# expLoRaBLE_Thing_Plus.net
KiCad netlist of a schematic drawn in EAGLE
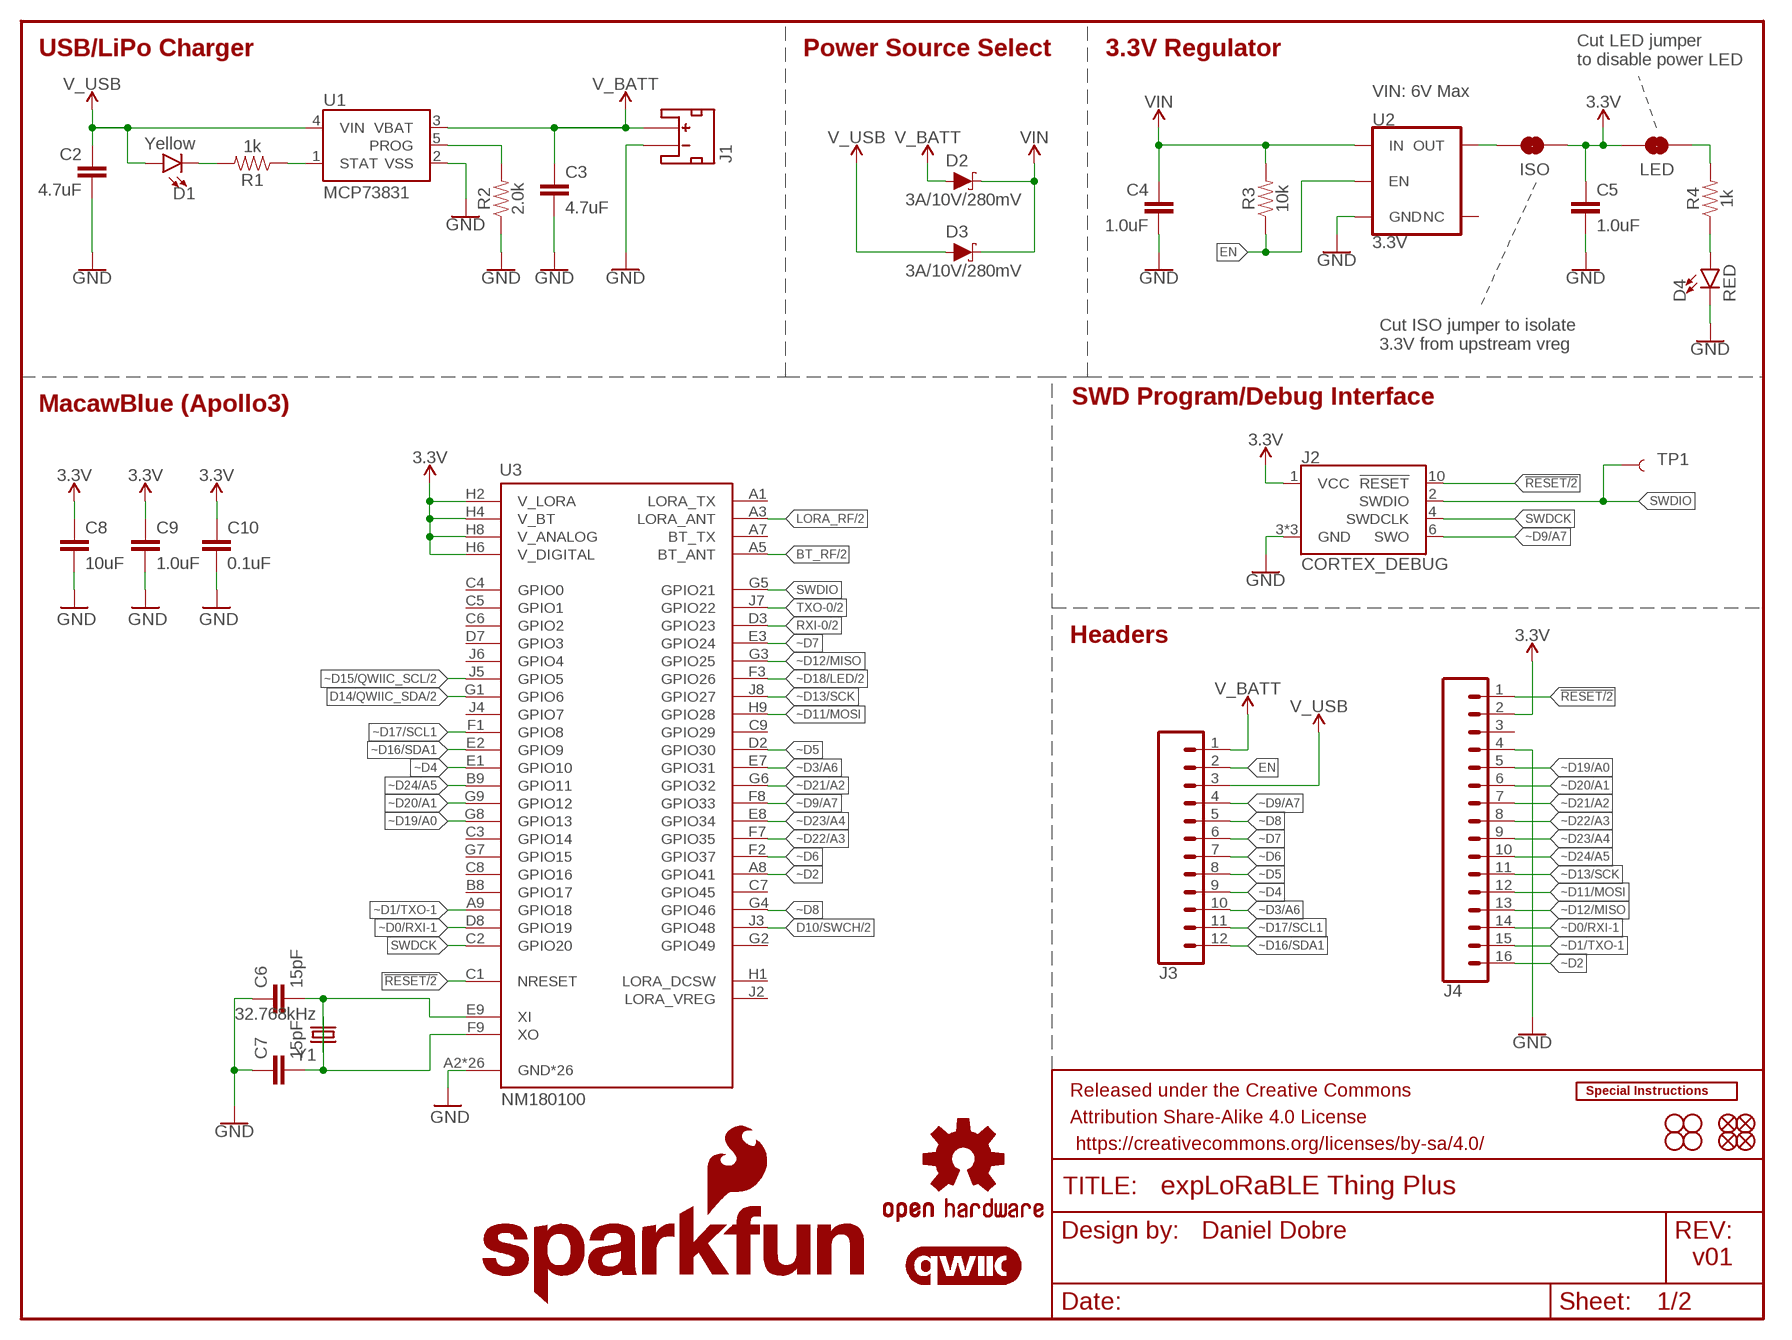
[diagram p0: schematic, sheet 1]
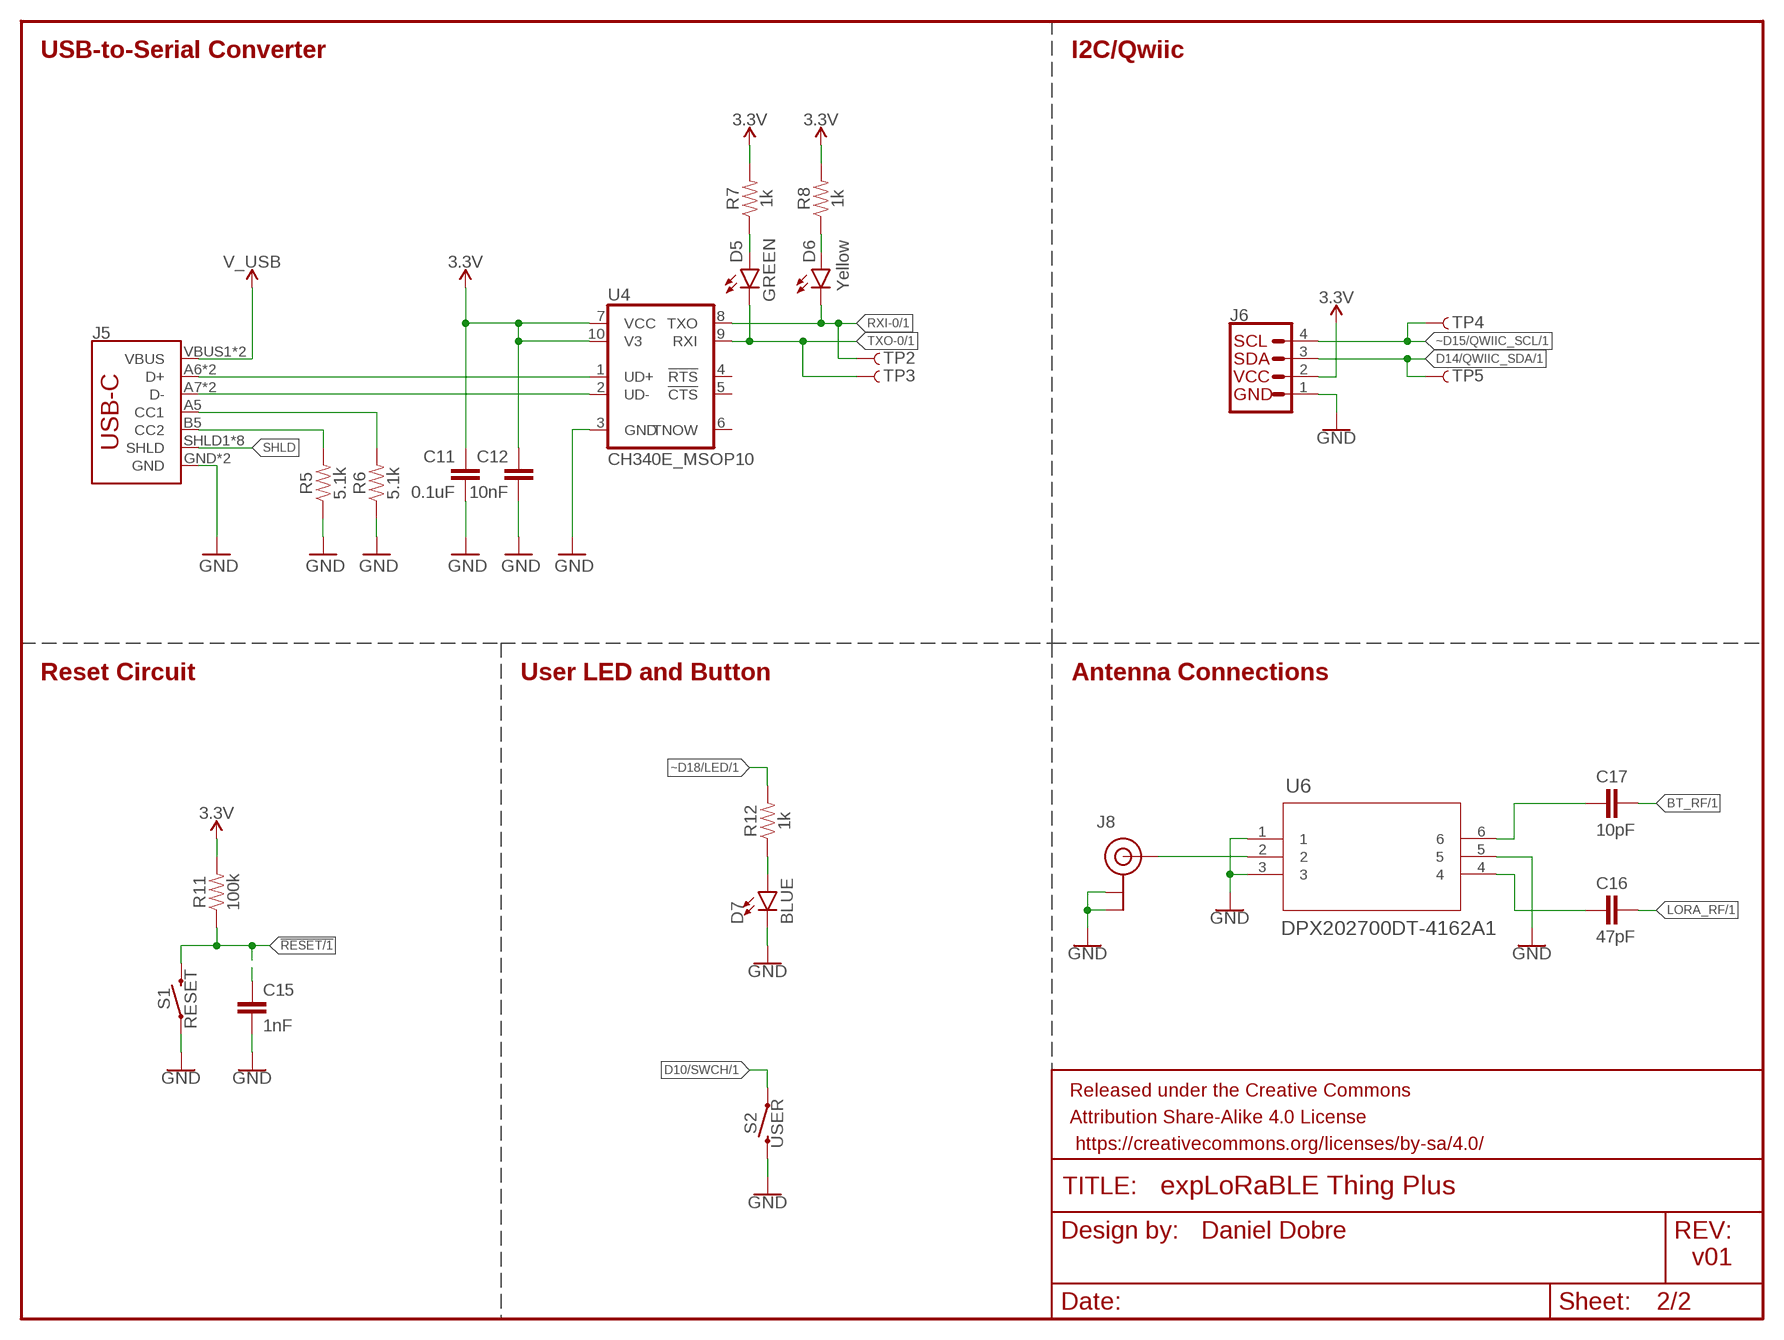
[diagram p1: schematic, sheet 2]

(export (version "E")
  (design (tool "Eeschema 10.0.6"))
  (components
    (comp (ref "C11")
      (value "0.1uF")
      (footprint "eagle-import:0603")
      (libsource (lib "eagle-import") (part "0.1UF-0603-25V-(+80/-20%)"))
    )
    (comp (ref "C12")
      (value "10nF")
      (footprint "eagle-import:0603")
      (libsource (lib "eagle-import") (part "10NF-0603-50V-10%"))
    )
    (comp (ref "C15")
      (value "1nF")
      (footprint "eagle-import:0603")
      (libsource (lib "eagle-import") (part "1.0NF/1000PF-0603-50V-10%"))
    )
    (comp (ref "C16")
      (value "47pF")
      (footprint "eagle-import:0603")
      (libsource (lib "eagle-import") (part "47PF-0603-50V-5%"))
    )
    (comp (ref "C17")
      (value "10pF")
      (footprint "eagle-import:0603")
      (libsource (lib "eagle-import") (part "10PF-0603-50V-5%"))
    )
    (comp (ref "D5")
      (value "GREEN")
      (footprint "eagle-import:LED-0603")
      (libsource (lib "eagle-import") (part "LED-GREEN0603"))
    )
    (comp (ref "D6")
      (value "Yellow")
      (footprint "eagle-import:LED-0603")
      (libsource (lib "eagle-import") (part "LED-YELLOW0603"))
    )
    (comp (ref "D7")
      (value "BLUE")
      (footprint "eagle-import:LED-0603")
      (libsource (lib "eagle-import") (part "LED-BLUE0603"))
    )
    (comp (ref "FRAME2")
      (value "FRAME-LETTERNO_PACKAGE")
      (footprint "eagle-import:DUMMY")
      (fields (field (name "DESIGNER") "Nobody"))
      (libsource (lib "eagle-import") (part "FRAME-LETTERNO_PACKAGE"))
    )
    (comp (ref "J5")
      (value "USB-C")
      (footprint "eagle-import:USB-C-16P")
      (libsource (lib "eagle-import") (part "USB_C2-LAYER"))
    )
    (comp (ref "J6")
      (value "QWIIC_CONNECTORJS-1MM")
      (footprint "eagle-import:JST04_1MM_RA")
      (libsource (lib "eagle-import") (part "QWIIC_CONNECTORJS-1MM"))
    )
    (comp (ref "J8")
      (value "U.FL")
      (footprint "eagle-import:U.FL")
      (libsource (lib "eagle-import") (part "U.FL"))
    )
    (comp (ref "R5")
      (value "5.1k")
      (footprint "eagle-import:0603")
      (libsource (lib "eagle-import") (part "5.1KOHM5.1KOHM-0603-1/10W-1%"))
    )
    (comp (ref "R6")
      (value "5.1k")
      (footprint "eagle-import:0603")
      (libsource (lib "eagle-import") (part "5.1KOHM5.1KOHM-0603-1/10W-1%"))
    )
    (comp (ref "R7")
      (value "1k")
      (footprint "eagle-import:0603")
      (libsource (lib "eagle-import") (part "1KOHM-0603-1/10W-1%"))
    )
    (comp (ref "R8")
      (value "1k")
      (footprint "eagle-import:0603")
      (libsource (lib "eagle-import") (part "1KOHM-0603-1/10W-1%"))
    )
    (comp (ref "R11")
      (value "100k")
      (footprint "eagle-import:0603")
      (libsource (lib "eagle-import") (part "100KOHM-0603-1/10W-1%"))
    )
    (comp (ref "R12")
      (value "1k")
      (footprint "eagle-import:0603")
      (libsource (lib "eagle-import") (part "1KOHM-0603-1/10W-1%"))
    )
    (comp (ref "S1")
      (value "RESET")
      (footprint "eagle-import:TACTILE_SWITCH_SMD_4.6X2.8MM")
      (libsource (lib "eagle-import") (part "MOMENTARY-SWITCH-SPST-SMD-4.6X2.8MM"))
    )
    (comp (ref "S2")
      (value "USER")
      (footprint "eagle-import:TACTILE_SWITCH_SMD_4.6X2.8MM")
      (libsource (lib "eagle-import") (part "MOMENTARY-SWITCH-SPST-SMD-4.6X2.8MM"))
    )
    (comp (ref "TP2")
      (value "TEST-POINTTP_15TH_THRU")
      (footprint "eagle-import:TP_15TH")
      (libsource (lib "eagle-import") (part "TEST-POINTTP_15TH_THRU"))
    )
    (comp (ref "TP3")
      (value "TEST-POINTTP_15TH_THRU")
      (footprint "eagle-import:TP_15TH")
      (libsource (lib "eagle-import") (part "TEST-POINTTP_15TH_THRU"))
    )
    (comp (ref "TP4")
      (value "TEST-POINTTP_15TH_THRU")
      (footprint "eagle-import:TP_15TH")
      (libsource (lib "eagle-import") (part "TEST-POINTTP_15TH_THRU"))
    )
    (comp (ref "TP5")
      (value "TEST-POINTTP_15TH_THRU")
      (footprint "eagle-import:TP_15TH")
      (libsource (lib "eagle-import") (part "TEST-POINTTP_15TH_THRU"))
    )
    (comp (ref "U4")
      (value "CH340E_MSOP10")
      (footprint "eagle-import:MSOP10")
      (libsource (lib "eagle-import") (part "CH340E_MSOP10"))
    )
    (comp (ref "U6")
      (value "DPX202700DT-4162A1")
      (footprint "eagle-import:RF_4060A1_TDK")
      (fields (field (name "COPYRIGHT") "Copyright (C) 2018 Accelerated Designs. All rights reserved"))
      (libsource (lib "eagle-import") (part "DPX202700DT-4162A1"))
    )
    (comp (ref "C2")
      (value "4.7uF")
      (footprint "eagle-import:0603")
      (libsource (lib "eagle-import") (part "4.7UF-0603-6.3V-(10%)"))
    )
    (comp (ref "C3")
      (value "4.7uF")
      (footprint "eagle-import:0603")
      (libsource (lib "eagle-import") (part "4.7UF-0603-6.3V-(10%)"))
    )
    (comp (ref "C4")
      (value "1.0uF")
      (footprint "eagle-import:0603")
      (libsource (lib "eagle-import") (part "1.0UF-0603-16V-10%"))
    )
    (comp (ref "C5")
      (value "1.0uF")
      (footprint "eagle-import:0603")
      (libsource (lib "eagle-import") (part "1.0UF-0603-16V-10%"))
    )
    (comp (ref "C6")
      (value "15pF")
      (footprint "eagle-import:0603")
      (libsource (lib "eagle-import") (part "15PF-0603-50V-5%"))
    )
    (comp (ref "C7")
      (value "15pF")
      (footprint "eagle-import:0603")
      (libsource (lib "eagle-import") (part "15PF-0603-50V-5%"))
    )
    (comp (ref "C8")
      (value "10uF")
      (footprint "eagle-import:0603")
      (libsource (lib "eagle-import") (part "10UF-0603-6.3V-20%"))
    )
    (comp (ref "C9")
      (value "1.0uF")
      (footprint "eagle-import:0603")
      (libsource (lib "eagle-import") (part "1.0UF-0603-16V-10%"))
    )
    (comp (ref "C10")
      (value "0.1uF")
      (footprint "eagle-import:0603")
      (libsource (lib "eagle-import") (part "0.1UF-0603-25V-(+80/-20%)"))
    )
    (comp (ref "D1")
      (value "Yellow")
      (footprint "eagle-import:LED-0603")
      (libsource (lib "eagle-import") (part "LED-YELLOW0603"))
    )
    (comp (ref "D2")
      (value "3A/10V/280mV")
      (footprint "eagle-import:SOD-323")
      (libsource (lib "eagle-import") (part "DIODE-SCHOTTKY-BAT60A"))
    )
    (comp (ref "D3")
      (value "3A/10V/280mV")
      (footprint "eagle-import:SOD-323")
      (libsource (lib "eagle-import") (part "DIODE-SCHOTTKY-BAT60A"))
    )
    (comp (ref "D4")
      (value "RED")
      (footprint "eagle-import:LED-0603")
      (libsource (lib "eagle-import") (part "LED-RED0603"))
    )
    (comp (ref "FD1")
      (value "FIDUCIALUFIDUCIAL")
      (footprint "eagle-import:FIDUCIAL-MICRO")
      (libsource (lib "eagle-import") (part "FIDUCIALUFIDUCIAL"))
    )
    (comp (ref "FD2")
      (value "FIDUCIALUFIDUCIAL")
      (footprint "eagle-import:FIDUCIAL-MICRO")
      (libsource (lib "eagle-import") (part "FIDUCIALUFIDUCIAL"))
    )
    (comp (ref "FD3")
      (value "FIDUCIALUFIDUCIAL")
      (footprint "eagle-import:FIDUCIAL-MICRO")
      (libsource (lib "eagle-import") (part "FIDUCIALUFIDUCIAL"))
    )
    (comp (ref "FD4")
      (value "FIDUCIALUFIDUCIAL")
      (footprint "eagle-import:FIDUCIAL-MICRO")
      (libsource (lib "eagle-import") (part "FIDUCIALUFIDUCIAL"))
    )
    (comp (ref "FRAME1")
      (value "FRAME-LETTER")
      (footprint "eagle-import:CREATIVE_COMMONS")
      (libsource (lib "eagle-import") (part "FRAME-LETTER"))
    )
    (comp (ref "H1")
      (value "STAND-OFF")
      (footprint "eagle-import:STAND-OFF")
      (libsource (lib "eagle-import") (part "STAND-OFF"))
    )
    (comp (ref "H2")
      (value "STAND-OFF")
      (footprint "eagle-import:STAND-OFF")
      (libsource (lib "eagle-import") (part "STAND-OFF"))
    )
    (comp (ref "H3")
      (value "STAND-OFF")
      (footprint "eagle-import:STAND-OFF")
      (libsource (lib "eagle-import") (part "STAND-OFF"))
    )
    (comp (ref "H4")
      (value "STAND-OFF")
      (footprint "eagle-import:STAND-OFF")
      (libsource (lib "eagle-import") (part "STAND-OFF"))
    )
    (comp (ref "ISO")
      (value "JUMPER-SMT_2_NC_TRACE_NO-SILK")
      (footprint "eagle-import:SMT-JUMPER_2_NC_TRACE_NO-SILK")
      (libsource (lib "eagle-import") (part "JUMPER-SMT_2_NC_TRACE_NO-SILK"))
    )
    (comp (ref "J1")
      (value "JST_2MM_MALE")
      (footprint "eagle-import:JST-2-SMD")
      (libsource (lib "eagle-import") (part "JST_2MM_MALE"))
    )
    (comp (ref "J2")
      (value "CORTEX_DEBUG")
      (footprint "eagle-import:2X5-PTH-1.27MM-NO_SILK")
      (libsource (lib "eagle-import") (part "CORTEX_DEBUG_MINIMUM_PTH_NS"))
    )
    (comp (ref "J3")
      (value "CONN_12SM_SQ_NO_SILK")
      (footprint "eagle-import:1X12_SM_SQ_NOSILK")
      (libsource (lib "eagle-import") (part "CONN_12SM_SQ_NO_SILK"))
    )
    (comp (ref "J4")
      (value "CONN_161X16_SM_SQ_NOSILK")
      (footprint "eagle-import:1X16_SM_SQ_NOSILK")
      (libsource (lib "eagle-import") (part "CONN_161X16_SM_SQ_NOSILK"))
    )
    (comp (ref "LED")
      (value "JUMPER-SMT_2_NC_TRACE_SILK")
      (footprint "eagle-import:SMT-JUMPER_2_NC_TRACE_SILK")
      (libsource (lib "eagle-import") (part "JUMPER-SMT_2_NC_TRACE_SILK"))
    )
    (comp (ref "LOGO1")
      (value "OSHW-LOGOS")
      (footprint "eagle-import:OSHW-LOGO-S")
      (libsource (lib "eagle-import") (part "OSHW-LOGOS"))
    )
    (comp (ref "LOGO2")
      (value "QWIIC_LOGO_5MM")
      (footprint "eagle-import:QWIIC_5MM")
      (libsource (lib "eagle-import") (part "QWIIC_LOGO_5MM"))
    )
    (comp (ref "LOGO3")
      (value "SFE_LOGO_NAME_FLAME.1_INCH")
      (footprint "eagle-import:SFE_LOGO_NAME_FLAME_.1")
      (libsource (lib "eagle-import") (part "SFE_LOGO_NAME_FLAME.1_INCH"))
    )
    (comp (ref "LOGO4")
      (value "SPECIAL_INSTRUCTIONS-ORDERING")
      (footprint "eagle-import:ORDERING_INSTRUCTIONS")
      (libsource (lib "eagle-import") (part "SPECIAL_INSTRUCTIONS-ORDERING"))
    )
    (comp (ref "R1")
      (value "1k")
      (footprint "eagle-import:0603")
      (libsource (lib "eagle-import") (part "1KOHM-0603-1/10W-1%"))
    )
    (comp (ref "R2")
      (value "2.0k")
      (footprint "eagle-import:0603")
      (libsource (lib "eagle-import") (part "2.0KOHM-0603-1/10W-5%"))
    )
    (comp (ref "R3")
      (value "10k")
      (footprint "eagle-import:0603")
      (libsource (lib "eagle-import") (part "10KOHM-0603-1/10W-1%"))
    )
    (comp (ref "R4")
      (value "1k")
      (footprint "eagle-import:0603")
      (libsource (lib "eagle-import") (part "1KOHM-0603-1/10W-1%"))
    )
    (comp (ref "TP1")
      (value "TEST-POINTTP_15TH_THRU")
      (footprint "eagle-import:TP_15TH")
      (libsource (lib "eagle-import") (part "SparkFun-Connectors_513_TEST-POINTTP_15TH_THRU"))
    )
    (comp (ref "U1")
      (value "MCP73831")
      (footprint "eagle-import:SOT23-5")
      (libsource (lib "eagle-import") (part "MCP73831"))
    )
    (comp (ref "U2")
      (value "3.3V")
      (footprint "eagle-import:SOT23-5")
      (libsource (lib "eagle-import") (part "V_REG_AP2112K-3.3V"))
    )
    (comp (ref "U3")
      (value "NM180100")
      (footprint "eagle-import:LGA81")
      (libsource (lib "eagle-import") (part "NM180100"))
    )
    (comp (ref "Y1")
      (value "32.768kHz")
      (footprint "eagle-import:CRYSTAL-SMD-3.2X1.5MM")
      (libsource (lib "eagle-import") (part "CRYSTAL-32.768KHZSMD-3.2X1.5"))
    )
  )
  (nets
    (net (code "1") (name "3.3V") (class "Default")
      (node (ref "C10") (pin "1") (pinfunction "1_1") (pintype "passive"))
      (node (ref "C11") (pin "1") (pinfunction "1_1") (pintype "passive"))
      (node (ref "C12") (pin "1") (pinfunction "1_1") (pintype "passive"))
      (node (ref "C5") (pin "1") (pinfunction "1_1") (pintype "passive"))
      (node (ref "C8") (pin "1") (pinfunction "1_1") (pintype "passive"))
      (node (ref "C9") (pin "1") (pinfunction "1_1") (pintype "passive"))
      (node (ref "ISO") (pin "1") (pinfunction "1_1") (pintype "passive"))
      (node (ref "J2") (pin "1") (pinfunction "VCC_1") (pintype "bidirectional"))
      (node (ref "J4") (pin "2") (pinfunction "2_2") (pintype "passive"))
      (node (ref "J6") (pin "2") (pinfunction "2_2") (pintype "power_in"))
      (node (ref "LED") (pin "2") (pinfunction "2_2") (pintype "passive"))
      (node (ref "R11") (pin "2") (pinfunction "2_2") (pintype "passive"))
      (node (ref "R7") (pin "2") (pinfunction "2_2") (pintype "passive"))
      (node (ref "R8") (pin "2") (pinfunction "2_2") (pintype "passive"))
      (node (ref "U3") (pin "H2") (pinfunction "V_LORA_H2") (pintype "bidirectional"))
      (node (ref "U3") (pin "H4") (pinfunction "V_BT_H4") (pintype "bidirectional"))
      (node (ref "U3") (pin "H6") (pinfunction "V_DIGITAL_H6") (pintype "bidirectional"))
      (node (ref "U3") (pin "H8") (pinfunction "V_ANALOG_H8") (pintype "bidirectional"))
      (node (ref "U4") (pin "10") (pinfunction "V3_10") (pintype "bidirectional"))
      (node (ref "U4") (pin "7") (pinfunction "VCC_7") (pintype "bidirectional"))
    )
    (net (code "2") (name "BT_RF") (class "Default")
      (node (ref "C17") (pin "1") (pinfunction "1_1") (pintype "passive"))
      (node (ref "U3") (pin "A5") (pinfunction "BT_ANT_A5") (pintype "bidirectional"))
    )
    (net (code "3") (name "D10{slash}SWCH") (class "Default")
      (node (ref "S2") (pin "1") (pinfunction "1_1") (pintype "passive"))
      (node (ref "S2") (pin "2") (pinfunction "1_2") (pintype "passive"))
      (node (ref "U3") (pin "J3") (pinfunction "GPIO48_J3") (pintype "bidirectional"))
    )
    (net (code "4") (name "D14{slash}QWIIC_SDA") (class "Default")
      (node (ref "J6") (pin "3") (pinfunction "3_3") (pintype "passive"))
      (node (ref "TP5") (pin "P$1") (pinfunction "1_P$1") (pintype "bidirectional"))
      (node (ref "U3") (pin "G1") (pinfunction "GPIO6_G1") (pintype "bidirectional"))
    )
    (net (code "5") (name "EN") (class "Default")
      (node (ref "J3") (pin "2") (pinfunction "2_2") (pintype "passive"))
      (node (ref "R3") (pin "1") (pinfunction "1_1") (pintype "passive"))
      (node (ref "U2") (pin "3") (pinfunction "EN_3") (pintype "input"))
    )
    (net (code "6") (name "GND") (class "Default")
      (node (ref "C10") (pin "2") (pinfunction "2_2") (pintype "passive"))
      (node (ref "C11") (pin "2") (pinfunction "2_2") (pintype "passive"))
      (node (ref "C12") (pin "2") (pinfunction "2_2") (pintype "passive"))
      (node (ref "C15") (pin "2") (pinfunction "2_2") (pintype "passive"))
      (node (ref "C2") (pin "2") (pinfunction "2_2") (pintype "passive"))
      (node (ref "C3") (pin "2") (pinfunction "2_2") (pintype "passive"))
      (node (ref "C4") (pin "2") (pinfunction "2_2") (pintype "passive"))
      (node (ref "C5") (pin "2") (pinfunction "2_2") (pintype "passive"))
      (node (ref "C6") (pin "1") (pinfunction "1_1") (pintype "passive"))
      (node (ref "C7") (pin "1") (pinfunction "1_1") (pintype "passive"))
      (node (ref "C8") (pin "2") (pinfunction "2_2") (pintype "passive"))
      (node (ref "C9") (pin "2") (pinfunction "2_2") (pintype "passive"))
      (node (ref "D4") (pin "C") (pinfunction "C_C") (pintype "passive"))
      (node (ref "D7") (pin "C") (pinfunction "C_C") (pintype "passive"))
      (node (ref "J1") (pin "1") (pinfunction "-_1") (pintype "bidirectional"))
      (node (ref "J2") (pin "3") (pinfunction "GND_3") (pintype "bidirectional"))
      (node (ref "J2") (pin "5") (pinfunction "GND_5") (pintype "bidirectional"))
      (node (ref "J2") (pin "9") (pinfunction "GND_9") (pintype "bidirectional"))
      (node (ref "J4") (pin "4") (pinfunction "4_4") (pintype "passive"))
      (node (ref "J5") (pin "GND") (pinfunction "GND_GND") (pintype "bidirectional"))
      (node (ref "J5") (pin "GND2") (pinfunction "GND_GND2") (pintype "bidirectional"))
      (node (ref "J6") (pin "1") (pinfunction "1_1") (pintype "power_in"))
      (node (ref "J8") (pin "1") (pinfunction "GND_1") (pintype "bidirectional"))
      (node (ref "J8") (pin "2") (pinfunction "GND_2") (pintype "bidirectional"))
      (node (ref "R2") (pin "1") (pinfunction "1_1") (pintype "passive"))
      (node (ref "R5") (pin "1") (pinfunction "1_1") (pintype "passive"))
      (node (ref "R6") (pin "1") (pinfunction "1_1") (pintype "passive"))
      (node (ref "S1") (pin "1") (pinfunction "1_1") (pintype "passive"))
      (node (ref "S1") (pin "2") (pinfunction "1_2") (pintype "passive"))
      (node (ref "S2") (pin "3") (pinfunction "2_3") (pintype "passive"))
      (node (ref "S2") (pin "4") (pinfunction "2_4") (pintype "passive"))
      (node (ref "U1") (pin "2") (pinfunction "VSS_2") (pintype "power_in"))
      (node (ref "U2") (pin "2") (pinfunction "GND_2") (pintype "input"))
      (node (ref "U3") (pin "A2") (pinfunction "GND*26_A2") (pintype "bidirectional"))
      (node (ref "U3") (pin "A4") (pinfunction "GND*26_A4") (pintype "bidirectional"))
      (node (ref "U3") (pin "A6") (pinfunction "GND*26_A6") (pintype "bidirectional"))
      (node (ref "U3") (pin "B1") (pinfunction "GND*26_B1") (pintype "bidirectional"))
      (node (ref "U3") (pin "B2") (pinfunction "GND*26_B2") (pintype "bidirectional"))
      (node (ref "U3") (pin "B3") (pinfunction "GND*26_B3") (pintype "bidirectional"))
      (node (ref "U3") (pin "B4") (pinfunction "GND*26_B4") (pintype "bidirectional"))
      (node (ref "U3") (pin "B5") (pinfunction "GND*26_B5") (pintype "bidirectional"))
      (node (ref "U3") (pin "B6") (pinfunction "GND*26_B6") (pintype "bidirectional"))
      (node (ref "U3") (pin "B7") (pinfunction "GND*26_B7") (pintype "bidirectional"))
      (node (ref "U3") (pin "D1") (pinfunction "GND*26_D1") (pintype "bidirectional"))
      (node (ref "U3") (pin "D4") (pinfunction "GND*26_D4") (pintype "bidirectional"))
      (node (ref "U3") (pin "D5") (pinfunction "GND*26_D5") (pintype "bidirectional"))
      (node (ref "U3") (pin "D6") (pinfunction "GND*26_D6") (pintype "bidirectional"))
      (node (ref "U3") (pin "D9") (pinfunction "GND*26_D9") (pintype "bidirectional"))
      (node (ref "U3") (pin "E4") (pinfunction "GND*26_E4") (pintype "bidirectional"))
      (node (ref "U3") (pin "E5") (pinfunction "GND*26_E5") (pintype "bidirectional"))
      (node (ref "U3") (pin "E6") (pinfunction "GND*26_E6") (pintype "bidirectional"))
      (node (ref "U3") (pin "F4") (pinfunction "GND*26_F4") (pintype "bidirectional"))
      (node (ref "U3") (pin "F5") (pinfunction "GND*26_F5") (pintype "bidirectional"))
      (node (ref "U3") (pin "F6") (pinfunction "GND*26_F6") (pintype "bidirectional"))
      (node (ref "U3") (pin "H3") (pinfunction "GND*26_H3") (pintype "bidirectional"))
      (node (ref "U3") (pin "H5") (pinfunction "GND*26_H5") (pintype "bidirectional"))
      (node (ref "U3") (pin "H7") (pinfunction "GND*26_H7") (pintype "bidirectional"))
      (node (ref "U3") (pin "J1") (pinfunction "GND*26_J1") (pintype "bidirectional"))
      (node (ref "U3") (pin "J9") (pinfunction "GND*26_J9") (pintype "bidirectional"))
      (node (ref "U4") (pin "3") (pinfunction "GND_3") (pintype "bidirectional"))
      (node (ref "U6") (pin "1") (pinfunction "1_1") (pintype "passive"))
      (node (ref "U6") (pin "3") (pinfunction "3_3") (pintype "passive"))
      (node (ref "U6") (pin "5") (pinfunction "5_5") (pintype "passive"))
    )
    (net (code "7") (name "LORA_RF") (class "Default")
      (node (ref "C16") (pin "1") (pinfunction "1_1") (pintype "passive"))
      (node (ref "U3") (pin "A3") (pinfunction "LORA_ANT_A3") (pintype "bidirectional"))
    )
    (net (code "8") (name "Net-(C16-Pad2)") (class "Default")
      (node (ref "C16") (pin "2") (pinfunction "2_2") (pintype "passive"))
      (node (ref "U6") (pin "4") (pinfunction "4_4") (pintype "passive"))
    )
    (net (code "9") (name "Net-(C17-Pad2)") (class "Default")
      (node (ref "C17") (pin "2") (pinfunction "2_2") (pintype "passive"))
      (node (ref "U6") (pin "6") (pinfunction "6_6") (pintype "passive"))
    )
    (net (code "10") (name "Net-(D1-PadC)") (class "Default")
      (node (ref "D1") (pin "C") (pinfunction "C_C") (pintype "passive"))
      (node (ref "R1") (pin "2") (pinfunction "2_2") (pintype "passive"))
    )
    (net (code "11") (name "Net-(D4-PadA)") (class "Default")
      (node (ref "D4") (pin "A") (pinfunction "A_A") (pintype "passive"))
      (node (ref "R4") (pin "1") (pinfunction "1_1") (pintype "passive"))
    )
    (net (code "12") (name "Net-(D5-PadA)") (class "Default")
      (node (ref "D5") (pin "A") (pinfunction "A_A") (pintype "passive"))
      (node (ref "R7") (pin "1") (pinfunction "1_1") (pintype "passive"))
    )
    (net (code "13") (name "Net-(D6-PadA)") (class "Default")
      (node (ref "D6") (pin "A") (pinfunction "A_A") (pintype "passive"))
      (node (ref "R8") (pin "1") (pinfunction "1_1") (pintype "passive"))
    )
    (net (code "14") (name "Net-(D7-PadA)") (class "Default")
      (node (ref "D7") (pin "A") (pinfunction "A_A") (pintype "passive"))
      (node (ref "R12") (pin "1") (pinfunction "1_1") (pintype "passive"))
    )
    (net (code "15") (name "Net-(J5-CC1)") (class "Default")
      (node (ref "J5") (pin "A5") (pinfunction "CC1_A5") (pintype "bidirectional"))
      (node (ref "R6") (pin "2") (pinfunction "2_2") (pintype "passive"))
    )
    (net (code "16") (name "Net-(J5-CC2)") (class "Default")
      (node (ref "J5") (pin "B5") (pinfunction "CC2_B5") (pintype "bidirectional"))
      (node (ref "R5") (pin "2") (pinfunction "2_2") (pintype "passive"))
    )
    (net (code "17") (name "Net-(J8-SIGNAL)") (class "Default")
      (node (ref "J8") (pin "FEED") (pinfunction "SIGNAL_FEED") (pintype "bidirectional"))
      (node (ref "U6") (pin "2") (pinfunction "2_2") (pintype "passive"))
    )
    (net (code "18") (name "Net-(LED-Pad1)") (class "Default")
      (node (ref "LED") (pin "1") (pinfunction "1_1") (pintype "passive"))
      (node (ref "R4") (pin "2") (pinfunction "2_2") (pintype "passive"))
    )
    (net (code "19") (name "Net-(U1-PROG)") (class "Default")
      (node (ref "R2") (pin "2") (pinfunction "2_2") (pintype "passive"))
      (node (ref "U1") (pin "5") (pinfunction "PROG_5") (pintype "input"))
    )
    (net (code "20") (name "Net-(U1-STAT)") (class "Default")
      (node (ref "R1") (pin "1") (pinfunction "1_1") (pintype "passive"))
      (node (ref "U1") (pin "1") (pinfunction "STAT_1") (pintype "output"))
    )
    (net (code "21") (name "Net-(U2-OUT)") (class "Default")
      (node (ref "ISO") (pin "2") (pinfunction "2_2") (pintype "passive"))
      (node (ref "U2") (pin "5") (pinfunction "OUT_5") (pintype "passive"))
    )
    (net (code "22") (name "Net-(U3-XI)") (class "Default")
      (node (ref "C6") (pin "2") (pinfunction "2_2") (pintype "passive"))
      (node (ref "U3") (pin "E9") (pinfunction "XI_E9") (pintype "bidirectional"))
      (node (ref "Y1") (pin "P$1") (pinfunction "1_P$1") (pintype "passive"))
    )
    (net (code "23") (name "Net-(U3-XO)") (class "Default")
      (node (ref "C7") (pin "2") (pinfunction "2_2") (pintype "passive"))
      (node (ref "U3") (pin "F9") (pinfunction "XO_F9") (pintype "bidirectional"))
      (node (ref "Y1") (pin "P$2") (pinfunction "2_P$2") (pintype "passive"))
    )
    (net (code "24") (name "Net-(U4-UD+)") (class "Default")
      (node (ref "J5") (pin "A6") (pinfunction "D+_A6") (pintype "bidirectional"))
      (node (ref "J5") (pin "B6") (pinfunction "D+_B6") (pintype "bidirectional"))
      (node (ref "U4") (pin "1") (pinfunction "UD+_1") (pintype "bidirectional"))
    )
    (net (code "25") (name "Net-(U4-UD-)") (class "Default")
      (node (ref "J5") (pin "A7") (pinfunction "D-_A7") (pintype "bidirectional"))
      (node (ref "J5") (pin "B7") (pinfunction "D-_B7") (pintype "bidirectional"))
      (node (ref "U4") (pin "2") (pinfunction "UD-_2") (pintype "bidirectional"))
    )
    (net (code "26") (name "RXI-0") (class "Default")
      (node (ref "D6") (pin "C") (pinfunction "C_C") (pintype "passive"))
      (node (ref "TP2") (pin "P$1") (pinfunction "1_P$1") (pintype "bidirectional"))
      (node (ref "U3") (pin "D3") (pinfunction "GPIO23_D3") (pintype "bidirectional"))
      (node (ref "U4") (pin "8") (pinfunction "TXO_8") (pintype "bidirectional"))
    )
    (net (code "27") (name "SHLD") (class "Default")
      (node (ref "J5") (pin "SHLD1") (pinfunction "SHLD_SHLD1") (pintype "bidirectional"))
      (node (ref "J5") (pin "SHLD2") (pinfunction "SHLD_SHLD2") (pintype "bidirectional"))
      (node (ref "J5") (pin "SHLD3") (pinfunction "SHLD_SHLD3") (pintype "bidirectional"))
      (node (ref "J5") (pin "SHLD4") (pinfunction "SHLD_SHLD4") (pintype "bidirectional"))
      (node (ref "J5") (pin "SHLD5") (pinfunction "SHLD_SHLD5") (pintype "bidirectional"))
      (node (ref "J5") (pin "SHLD6") (pinfunction "SHLD_SHLD6") (pintype "bidirectional"))
      (node (ref "J5") (pin "SHLD7") (pinfunction "SHLD_SHLD7") (pintype "bidirectional"))
      (node (ref "J5") (pin "SHLD8") (pinfunction "SHLD_SHLD8") (pintype "bidirectional"))
    )
    (net (code "28") (name "SWDCK") (class "Default")
      (node (ref "J2") (pin "4") (pinfunction "SWDCLK_4") (pintype "bidirectional"))
      (node (ref "U3") (pin "C2") (pinfunction "GPIO20_C2") (pintype "bidirectional"))
    )
    (net (code "29") (name "SWDIO") (class "Default")
      (node (ref "J2") (pin "2") (pinfunction "SWDIO_2") (pintype "bidirectional"))
      (node (ref "TP1") (pin "P$1") (pinfunction "1_P$1") (pintype "bidirectional"))
      (node (ref "U3") (pin "G5") (pinfunction "GPIO21_G5") (pintype "bidirectional"))
    )
    (net (code "30") (name "TXO-0") (class "Default")
      (node (ref "D5") (pin "C") (pinfunction "C_C") (pintype "passive"))
      (node (ref "TP3") (pin "P$1") (pinfunction "1_P$1") (pintype "bidirectional"))
      (node (ref "U3") (pin "J7") (pinfunction "GPIO22_J7") (pintype "bidirectional"))
      (node (ref "U4") (pin "9") (pinfunction "RXI_9") (pintype "bidirectional"))
    )
    (net (code "31") (name "VIN") (class "Default")
      (node (ref "C4") (pin "1") (pinfunction "1_1") (pintype "passive"))
      (node (ref "D2") (pin "C") (pinfunction "C_C") (pintype "passive"))
      (node (ref "D3") (pin "C") (pinfunction "C_C") (pintype "passive"))
      (node (ref "R3") (pin "2") (pinfunction "2_2") (pintype "passive"))
      (node (ref "U2") (pin "1") (pinfunction "IN_1") (pintype "input"))
    )
    (net (code "32") (name "V_BATT") (class "Default")
      (node (ref "C3") (pin "1") (pinfunction "1_1") (pintype "passive"))
      (node (ref "D2") (pin "A") (pinfunction "A_A") (pintype "passive"))
      (node (ref "J1") (pin "2") (pinfunction "+_2") (pintype "bidirectional"))
      (node (ref "J3") (pin "1") (pinfunction "1_1") (pintype "passive"))
      (node (ref "U1") (pin "3") (pinfunction "VBAT_3") (pintype "power_in"))
    )
    (net (code "33") (name "V_USB") (class "Default")
      (node (ref "C2") (pin "1") (pinfunction "1_1") (pintype "passive"))
      (node (ref "D1") (pin "A") (pinfunction "A_A") (pintype "passive"))
      (node (ref "D3") (pin "A") (pinfunction "A_A") (pintype "passive"))
      (node (ref "J3") (pin "3") (pinfunction "3_3") (pintype "passive"))
      (node (ref "J5") (pin "VBUS1") (pinfunction "VBUS_VBUS1") (pintype "bidirectional"))
      (node (ref "J5") (pin "VBUS2") (pinfunction "VBUS_VBUS2") (pintype "bidirectional"))
      (node (ref "U1") (pin "4") (pinfunction "VIN_4") (pintype "power_in"))
    )
    (net (code "34") (name "unconnected-(J1-PAD1-PadNC1)") (class "Default")
      (node (ref "J1") (pin "NC1") (pinfunction "PAD1_NC1") (pintype "bidirectional"))
    )
    (net (code "35") (name "unconnected-(J1-PAD2-PadNC2)") (class "Default")
      (node (ref "J1") (pin "NC2") (pinfunction "PAD2_NC2") (pintype "bidirectional"))
    )
    (net (code "36") (name "unconnected-(J4-Pad3)") (class "Default")
      (node (ref "J4") (pin "3") (pinfunction "3_3") (pintype "passive"))
    )
    (net (code "37") (name "unconnected-(U2-NC-Pad4)") (class "Default")
      (node (ref "U2") (pin "4") (pinfunction "NC_4") (pintype "no_connect"))
    )
    (net (code "38") (name "unconnected-(U3-BT_TX-PadA7)") (class "Default")
      (node (ref "U3") (pin "A7") (pinfunction "BT_TX_A7") (pintype "bidirectional"))
    )
    (net (code "39") (name "unconnected-(U3-GPIO0-PadC4)") (class "Default")
      (node (ref "U3") (pin "C4") (pinfunction "GPIO0_C4") (pintype "bidirectional"))
    )
    (net (code "40") (name "unconnected-(U3-GPIO1-PadC5)") (class "Default")
      (node (ref "U3") (pin "C5") (pinfunction "GPIO1_C5") (pintype "bidirectional"))
    )
    (net (code "41") (name "unconnected-(U3-GPIO2-PadC6)") (class "Default")
      (node (ref "U3") (pin "C6") (pinfunction "GPIO2_C6") (pintype "bidirectional"))
    )
    (net (code "42") (name "unconnected-(U3-GPIO3-PadD7)") (class "Default")
      (node (ref "U3") (pin "D7") (pinfunction "GPIO3_D7") (pintype "bidirectional"))
    )
    (net (code "43") (name "unconnected-(U3-GPIO4-PadJ6)") (class "Default")
      (node (ref "U3") (pin "J6") (pinfunction "GPIO4_J6") (pintype "bidirectional"))
    )
    (net (code "44") (name "unconnected-(U3-GPIO7-PadJ4)") (class "Default")
      (node (ref "U3") (pin "J4") (pinfunction "GPIO7_J4") (pintype "bidirectional"))
    )
    (net (code "45") (name "unconnected-(U3-GPIO14-PadC3)") (class "Default")
      (node (ref "U3") (pin "C3") (pinfunction "GPIO14_C3") (pintype "bidirectional"))
    )
    (net (code "46") (name "unconnected-(U3-GPIO15-PadG7)") (class "Default")
      (node (ref "U3") (pin "G7") (pinfunction "GPIO15_G7") (pintype "bidirectional"))
    )
    (net (code "47") (name "unconnected-(U3-GPIO16-PadC8)") (class "Default")
      (node (ref "U3") (pin "C8") (pinfunction "GPIO16_C8") (pintype "bidirectional"))
    )
    (net (code "48") (name "unconnected-(U3-GPIO17-PadB8)") (class "Default")
      (node (ref "U3") (pin "B8") (pinfunction "GPIO17_B8") (pintype "bidirectional"))
    )
    (net (code "49") (name "unconnected-(U3-GPIO29-PadC9)") (class "Default")
      (node (ref "U3") (pin "C9") (pinfunction "GPIO29_C9") (pintype "bidirectional"))
    )
    (net (code "50") (name "unconnected-(U3-GPIO45-PadC7)") (class "Default")
      (node (ref "U3") (pin "C7") (pinfunction "GPIO45_C7") (pintype "bidirectional"))
    )
    (net (code "51") (name "unconnected-(U3-GPIO49-PadG2)") (class "Default")
      (node (ref "U3") (pin "G2") (pinfunction "GPIO49_G2") (pintype "bidirectional"))
    )
    (net (code "52") (name "unconnected-(U3-LORA_DCSW-PadH1)") (class "Default")
      (node (ref "U3") (pin "H1") (pinfunction "LORA_DCSW_H1") (pintype "bidirectional"))
    )
    (net (code "53") (name "unconnected-(U3-LORA_TX-PadA1)") (class "Default")
      (node (ref "U3") (pin "A1") (pinfunction "LORA_TX_A1") (pintype "bidirectional"))
    )
    (net (code "54") (name "unconnected-(U3-LORA_VREG-PadJ2)") (class "Default")
      (node (ref "U3") (pin "J2") (pinfunction "LORA_VREG_J2") (pintype "bidirectional"))
    )
    (net (code "55") (name "unconnected-(U4-TNOW-Pad6)") (class "Default")
      (node (ref "U4") (pin "6") (pinfunction "TNOW_6") (pintype "bidirectional"))
    )
    (net (code "56") (name "unconnected-(U4-~{CTS}-Pad5)") (class "Default")
      (node (ref "U4") (pin "5") (pinfunction "~{CTS}_5") (pintype "bidirectional"))
    )
    (net (code "57") (name "unconnected-(U4-~{RTS}-Pad4)") (class "Default")
      (node (ref "U4") (pin "4") (pinfunction "~{RTS}_4") (pintype "bidirectional"))
    )
    (net (code "58") (name "~{D0{slash}RXI-1}") (class "Default")
      (node (ref "J4") (pin "14") (pinfunction "14_14") (pintype "passive"))
      (node (ref "U3") (pin "D8") (pinfunction "GPIO19_D8") (pintype "bidirectional"))
    )
    (net (code "59") (name "~{D1{slash}TXO-1}") (class "Default")
      (node (ref "J4") (pin "15") (pinfunction "15_15") (pintype "passive"))
      (node (ref "U3") (pin "A9") (pinfunction "GPIO18_A9") (pintype "bidirectional"))
    )
    (net (code "60") (name "~{D2}") (class "Default")
      (node (ref "J4") (pin "16") (pinfunction "16_16") (pintype "passive"))
      (node (ref "U3") (pin "A8") (pinfunction "GPIO41_A8") (pintype "bidirectional"))
    )
    (net (code "61") (name "~{D3{slash}A6}") (class "Default")
      (node (ref "J3") (pin "10") (pinfunction "10_10") (pintype "passive"))
      (node (ref "U3") (pin "E7") (pinfunction "GPIO31_E7") (pintype "bidirectional"))
    )
    (net (code "62") (name "~{D4}") (class "Default")
      (node (ref "J3") (pin "9") (pinfunction "9_9") (pintype "passive"))
      (node (ref "U3") (pin "E1") (pinfunction "GPIO10_E1") (pintype "bidirectional"))
    )
    (net (code "63") (name "~{D5}") (class "Default")
      (node (ref "J3") (pin "8") (pinfunction "8_8") (pintype "passive"))
      (node (ref "U3") (pin "D2") (pinfunction "GPIO30_D2") (pintype "bidirectional"))
    )
    (net (code "64") (name "~{D6}") (class "Default")
      (node (ref "J3") (pin "7") (pinfunction "7_7") (pintype "passive"))
      (node (ref "U3") (pin "F2") (pinfunction "GPIO37_F2") (pintype "bidirectional"))
    )
    (net (code "65") (name "~{D7}") (class "Default")
      (node (ref "J3") (pin "6") (pinfunction "6_6") (pintype "passive"))
      (node (ref "U3") (pin "E3") (pinfunction "GPIO24_E3") (pintype "bidirectional"))
    )
    (net (code "66") (name "~{D8}") (class "Default")
      (node (ref "J3") (pin "5") (pinfunction "5_5") (pintype "passive"))
      (node (ref "U3") (pin "G4") (pinfunction "GPIO46_G4") (pintype "bidirectional"))
    )
    (net (code "67") (name "~{D9{slash}A7}") (class "Default")
      (node (ref "J2") (pin "6") (pinfunction "SWO_6") (pintype "bidirectional"))
      (node (ref "J3") (pin "4") (pinfunction "4_4") (pintype "passive"))
      (node (ref "U3") (pin "F8") (pinfunction "GPIO33_F8") (pintype "bidirectional"))
    )
    (net (code "68") (name "~{D11{slash}MOSI}") (class "Default")
      (node (ref "J4") (pin "12") (pinfunction "12_12") (pintype "passive"))
      (node (ref "U3") (pin "H9") (pinfunction "GPIO28_H9") (pintype "bidirectional"))
    )
    (net (code "69") (name "~{D12{slash}MISO}") (class "Default")
      (node (ref "J4") (pin "13") (pinfunction "13_13") (pintype "passive"))
      (node (ref "U3") (pin "G3") (pinfunction "GPIO25_G3") (pintype "bidirectional"))
    )
    (net (code "70") (name "~{D13{slash}SCK}") (class "Default")
      (node (ref "J4") (pin "11") (pinfunction "11_11") (pintype "passive"))
      (node (ref "U3") (pin "J8") (pinfunction "GPIO27_J8") (pintype "bidirectional"))
    )
    (net (code "71") (name "~{D15{slash}QWIIC_SCL}") (class "Default")
      (node (ref "J6") (pin "4") (pinfunction "4_4") (pintype "passive"))
      (node (ref "TP4") (pin "P$1") (pinfunction "1_P$1") (pintype "bidirectional"))
      (node (ref "U3") (pin "J5") (pinfunction "GPIO5_J5") (pintype "bidirectional"))
    )
    (net (code "72") (name "~{D16{slash}SDA1}") (class "Default")
      (node (ref "J3") (pin "12") (pinfunction "12_12") (pintype "passive"))
      (node (ref "U3") (pin "E2") (pinfunction "GPIO9_E2") (pintype "bidirectional"))
    )
    (net (code "73") (name "~{D17{slash}SCL1}") (class "Default")
      (node (ref "J3") (pin "11") (pinfunction "11_11") (pintype "passive"))
      (node (ref "U3") (pin "F1") (pinfunction "GPIO8_F1") (pintype "bidirectional"))
    )
    (net (code "74") (name "~{D18{slash}LED}") (class "Default")
      (node (ref "R12") (pin "2") (pinfunction "2_2") (pintype "passive"))
      (node (ref "U3") (pin "F3") (pinfunction "GPIO26_F3") (pintype "bidirectional"))
    )
    (net (code "75") (name "~{D19{slash}A0}") (class "Default")
      (node (ref "J4") (pin "5") (pinfunction "5_5") (pintype "passive"))
      (node (ref "U3") (pin "G8") (pinfunction "GPIO13_G8") (pintype "bidirectional"))
    )
    (net (code "76") (name "~{D20{slash}A1}") (class "Default")
      (node (ref "J4") (pin "6") (pinfunction "6_6") (pintype "passive"))
      (node (ref "U3") (pin "G9") (pinfunction "GPIO12_G9") (pintype "bidirectional"))
    )
    (net (code "77") (name "~{D21{slash}A2}") (class "Default")
      (node (ref "J4") (pin "7") (pinfunction "7_7") (pintype "passive"))
      (node (ref "U3") (pin "G6") (pinfunction "GPIO32_G6") (pintype "bidirectional"))
    )
    (net (code "78") (name "~{D22{slash}A3}") (class "Default")
      (node (ref "J4") (pin "8") (pinfunction "8_8") (pintype "passive"))
      (node (ref "U3") (pin "F7") (pinfunction "GPIO35_F7") (pintype "bidirectional"))
    )
    (net (code "79") (name "~{D23{slash}A4}") (class "Default")
      (node (ref "J4") (pin "9") (pinfunction "9_9") (pintype "passive"))
      (node (ref "U3") (pin "E8") (pinfunction "GPIO34_E8") (pintype "bidirectional"))
    )
    (net (code "80") (name "~{D24{slash}A5}") (class "Default")
      (node (ref "J4") (pin "10") (pinfunction "10_10") (pintype "passive"))
      (node (ref "U3") (pin "B9") (pinfunction "GPIO11_B9") (pintype "bidirectional"))
    )
    (net (code "81") (name "~{RESET}") (class "Default")
      (node (ref "C15") (pin "1") (pinfunction "1_1") (pintype "passive"))
      (node (ref "J2") (pin "10") (pinfunction "~{RESET}_10") (pintype "bidirectional"))
      (node (ref "J4") (pin "1") (pinfunction "1_1") (pintype "passive"))
      (node (ref "R11") (pin "1") (pinfunction "1_1") (pintype "passive"))
      (node (ref "S1") (pin "3") (pinfunction "2_3") (pintype "passive"))
      (node (ref "S1") (pin "4") (pinfunction "2_4") (pintype "passive"))
      (node (ref "U3") (pin "C1") (pinfunction "NRESET_C1") (pintype "bidirectional"))
    )
  )
)
